# 18_HD4_PUMP.net
KiCad netlist of a schematic drawn in Altium Designer
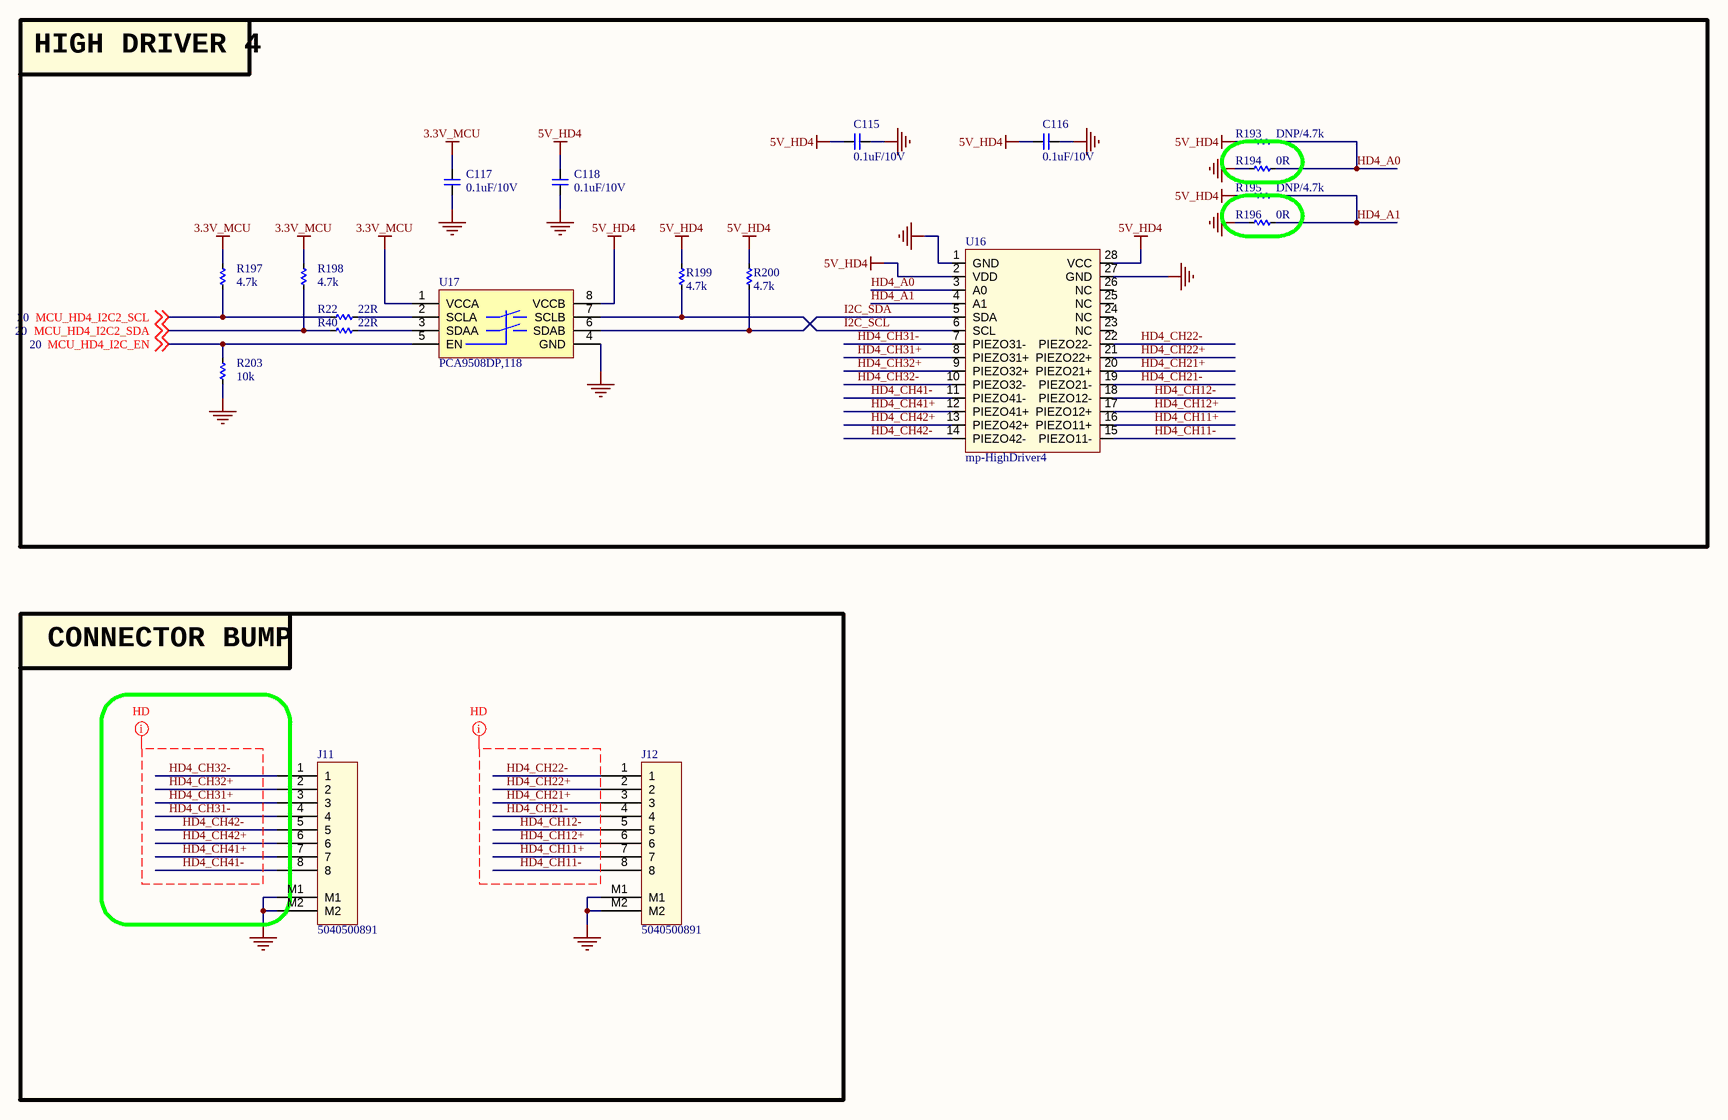
[diagram p0: 18_HD4_PUMP.SchDoc]

(export (version "E")
  (design (tool "Eeschema 10.0.6"))
  (components
    (comp (ref "C115")
      (value "0.1uF/10V")
      (footprint "CAP_C_1005X60")
      (description "CAP")
      (libsource (lib "LABLIB") (part "_CAP_C_2"))
    )
    (comp (ref "C116")
      (value "0.1uF/10V")
      (footprint "CAP_C_1005X60")
      (description "CAP")
      (libsource (lib "LABLIB") (part "_CAP_C_2"))
    )
    (comp (ref "C117")
      (value "0.1uF/10V")
      (footprint "CAP_C_1005X60")
      (description "CAP")
      (libsource (lib "LABLIB") (part "_CAP_C_2"))
    )
    (comp (ref "C118")
      (value "0.1uF/10V")
      (footprint "CAP_C_1005X60")
      (description "CAP")
      (libsource (lib "LABLIB") (part "_CAP_C_2"))
    )
    (comp (ref "J11")
      (value "5040500891")
      (footprint "MOLEX_5040500891")
      (libsource (lib "LABLIB") (part "Header 8x1_2M"))
    )
    (comp (ref "J12")
      (value "5040500891")
      (footprint "MOLEX_5040500891")
      (libsource (lib "LABLIB") (part "Header 8x1_2M"))
    )
    (comp (ref "R22")
      (value "22R")
      (footprint "RES_C_1005X40")
      (description "RES")
      (libsource (lib "LABLIB") (part "_RES_B_2"))
    )
    (comp (ref "R40")
      (value "22R")
      (footprint "RES_C_1005X40")
      (description "RES")
      (libsource (lib "LABLIB") (part "_RES_B_2"))
    )
    (comp (ref "R193")
      (value "DNP/4.7k")
      (footprint "RES_C_1005X40")
      (description "RES")
      (libsource (lib "LABLIB") (part "_RES_B_2"))
    )
    (comp (ref "R194")
      (value "0R")
      (footprint "RES_C_1005X40")
      (description "RES")
      (libsource (lib "LABLIB") (part "_RES_B_2"))
    )
    (comp (ref "R195")
      (value "DNP/4.7k")
      (footprint "RES_C_1005X40")
      (description "RES")
      (libsource (lib "LABLIB") (part "_RES_B_2"))
    )
    (comp (ref "R196")
      (value "0R")
      (footprint "RES_C_1005X40")
      (description "RES")
      (libsource (lib "LABLIB") (part "_RES_B_2"))
    )
    (comp (ref "R197")
      (value "4.7k")
      (footprint "RES_C_1005X40")
      (description "RES")
      (libsource (lib "LABLIB") (part "_RES_B_2"))
    )
    (comp (ref "R198")
      (value "4.7k")
      (footprint "RES_C_1005X40")
      (description "RES")
      (libsource (lib "LABLIB") (part "_RES_B_2"))
    )
    (comp (ref "R199")
      (value "4.7k")
      (footprint "RES_C_1005X40")
      (description "RES")
      (libsource (lib "LABLIB") (part "_RES_B_2"))
    )
    (comp (ref "R200")
      (value "4.7k")
      (footprint "RES_C_1005X40")
      (description "RES")
      (libsource (lib "LABLIB") (part "_RES_B_2"))
    )
    (comp (ref "R203")
      (value "10k")
      (footprint "RES_C_1005X40")
      (description "RES")
      (libsource (lib "LABLIB") (part "_RES_B_2"))
    )
    (comp (ref "U16")
      (value "mp-HighDriver4")
      (footprint "MP_HIGHDRIVER4")
      (libsource (lib "new_component") (part "mp_HighDriver4"))
    )
    (comp (ref "U17")
      (value "PCA9508DP,118")
      (footprint "TSOP8")
      (libsource (lib "EXP_HW_V3") (part "PCA9508DP,118"))
    )
  )
  (nets
    (net (code "1") (name "/HD4_A0") (class "Default")
      (node (ref "R193") (pin "2") (pinfunction "2_2") (pintype "passive"))
      (node (ref "R194") (pin "2") (pinfunction "2_2") (pintype "passive"))
      (node (ref "U16") (pin "3") (pinfunction "A0_3") (pintype "passive"))
    )
    (net (code "2") (name "/HD4_A1") (class "Default")
      (node (ref "R195") (pin "2") (pinfunction "2_2") (pintype "passive"))
      (node (ref "R196") (pin "2") (pinfunction "2_2") (pintype "passive"))
      (node (ref "U16") (pin "4") (pinfunction "A1_4") (pintype "passive"))
    )
    (net (code "3") (name "/HD4_CH11+") (class "Default")
      (node (ref "J12") (pin "7") (pinfunction "7_7") (pintype "passive"))
      (node (ref "U16") (pin "16") (pinfunction "PIEZO11+_16") (pintype "passive"))
    )
    (net (code "4") (name "/HD4_CH11-") (class "Default")
      (node (ref "J12") (pin "8") (pinfunction "8_8") (pintype "passive"))
      (node (ref "U16") (pin "15") (pinfunction "PIEZO11-_15") (pintype "passive"))
    )
    (net (code "5") (name "/HD4_CH12+") (class "Default")
      (node (ref "J12") (pin "6") (pinfunction "6_6") (pintype "passive"))
      (node (ref "U16") (pin "17") (pinfunction "PIEZO12+_17") (pintype "passive"))
    )
    (net (code "6") (name "/HD4_CH12-") (class "Default")
      (node (ref "J12") (pin "5") (pinfunction "5_5") (pintype "passive"))
      (node (ref "U16") (pin "18") (pinfunction "PIEZO12-_18") (pintype "passive"))
    )
    (net (code "7") (name "/HD4_CH21+") (class "Default")
      (node (ref "J12") (pin "3") (pinfunction "3_3") (pintype "passive"))
      (node (ref "U16") (pin "20") (pinfunction "PIEZO21+_20") (pintype "passive"))
    )
    (net (code "8") (name "/HD4_CH21-") (class "Default")
      (node (ref "J12") (pin "4") (pinfunction "4_4") (pintype "passive"))
      (node (ref "U16") (pin "19") (pinfunction "PIEZO21-_19") (pintype "passive"))
    )
    (net (code "9") (name "/HD4_CH22+") (class "Default")
      (node (ref "J12") (pin "2") (pinfunction "2_2") (pintype "passive"))
      (node (ref "U16") (pin "21") (pinfunction "PIEZO22+_21") (pintype "passive"))
    )
    (net (code "10") (name "/HD4_CH22-") (class "Default")
      (node (ref "J12") (pin "1") (pinfunction "1_1") (pintype "passive"))
      (node (ref "U16") (pin "22") (pinfunction "PIEZO22-_22") (pintype "passive"))
    )
    (net (code "11") (name "/HD4_CH31+") (class "Default")
      (node (ref "J11") (pin "3") (pinfunction "3_3") (pintype "passive"))
      (node (ref "U16") (pin "8") (pinfunction "PIEZO31+_8") (pintype "passive"))
    )
    (net (code "12") (name "/HD4_CH31-") (class "Default")
      (node (ref "J11") (pin "4") (pinfunction "4_4") (pintype "passive"))
      (node (ref "U16") (pin "7") (pinfunction "PIEZO31-_7") (pintype "passive"))
    )
    (net (code "13") (name "/HD4_CH32+") (class "Default")
      (node (ref "J11") (pin "2") (pinfunction "2_2") (pintype "passive"))
      (node (ref "U16") (pin "9") (pinfunction "PIEZO32+_9") (pintype "passive"))
    )
    (net (code "14") (name "/HD4_CH32-") (class "Default")
      (node (ref "J11") (pin "1") (pinfunction "1_1") (pintype "passive"))
      (node (ref "U16") (pin "10") (pinfunction "PIEZO32-_10") (pintype "passive"))
    )
    (net (code "15") (name "/HD4_CH41+") (class "Default")
      (node (ref "J11") (pin "7") (pinfunction "7_7") (pintype "passive"))
      (node (ref "U16") (pin "12") (pinfunction "PIEZO41+_12") (pintype "passive"))
    )
    (net (code "16") (name "/HD4_CH41-") (class "Default")
      (node (ref "J11") (pin "8") (pinfunction "8_8") (pintype "passive"))
      (node (ref "U16") (pin "11") (pinfunction "PIEZO41-_11") (pintype "passive"))
    )
    (net (code "17") (name "/HD4_CH42+") (class "Default")
      (node (ref "J11") (pin "6") (pinfunction "6_6") (pintype "passive"))
      (node (ref "U16") (pin "13") (pinfunction "PIEZO42+_13") (pintype "passive"))
    )
    (net (code "18") (name "/HD4_CH42-") (class "Default")
      (node (ref "J11") (pin "5") (pinfunction "5_5") (pintype "passive"))
      (node (ref "U16") (pin "14") (pinfunction "PIEZO42-_14") (pintype "passive"))
    )
    (net (code "19") (name "/I2C_SCL") (class "Default")
      (node (ref "R199") (pin "2") (pinfunction "2_2") (pintype "passive"))
      (node (ref "U16") (pin "6") (pinfunction "SCL_6") (pintype "passive"))
      (node (ref "U17") (pin "7") (pinfunction "SCLB_7") (pintype "passive"))
    )
    (net (code "20") (name "/I2C_SDA") (class "Default")
      (node (ref "R200") (pin "2") (pinfunction "2_2") (pintype "passive"))
      (node (ref "U16") (pin "5") (pinfunction "SDA_5") (pintype "passive"))
      (node (ref "U17") (pin "6") (pinfunction "SDAB_6") (pintype "passive"))
    )
    (net (code "21") (name "3.3V_MCU") (class "Default")
      (node (ref "C117") (pin "2") (pinfunction "2_2") (pintype "passive"))
      (node (ref "R197") (pin "1") (pinfunction "1_1") (pintype "passive"))
      (node (ref "R198") (pin "1") (pinfunction "1_1") (pintype "passive"))
      (node (ref "U17") (pin "1") (pinfunction "VCCA_1") (pintype "passive"))
    )
    (net (code "22") (name "5V_HD4") (class "Default")
      (node (ref "C115") (pin "2") (pinfunction "2_2") (pintype "passive"))
      (node (ref "C116") (pin "2") (pinfunction "2_2") (pintype "passive"))
      (node (ref "C118") (pin "2") (pinfunction "2_2") (pintype "passive"))
      (node (ref "R193") (pin "1") (pinfunction "1_1") (pintype "passive"))
      (node (ref "R195") (pin "1") (pinfunction "1_1") (pintype "passive"))
      (node (ref "R199") (pin "1") (pinfunction "1_1") (pintype "passive"))
      (node (ref "R200") (pin "1") (pinfunction "1_1") (pintype "passive"))
      (node (ref "U16") (pin "2") (pinfunction "VDD_2") (pintype "power_in"))
      (node (ref "U16") (pin "28") (pinfunction "VCC_28") (pintype "power_in"))
      (node (ref "U17") (pin "8") (pinfunction "VCCB_8") (pintype "passive"))
    )
    (net (code "23") (name "GND") (class "Default")
      (node (ref "C115") (pin "1") (pinfunction "1_1") (pintype "passive"))
      (node (ref "C116") (pin "1") (pinfunction "1_1") (pintype "passive"))
      (node (ref "C117") (pin "1") (pinfunction "1_1") (pintype "passive"))
      (node (ref "C118") (pin "1") (pinfunction "1_1") (pintype "passive"))
      (node (ref "J11") (pin "M1") (pinfunction "M1_M1") (pintype "passive"))
      (node (ref "J11") (pin "M2") (pinfunction "M2_M2") (pintype "passive"))
      (node (ref "J12") (pin "M1") (pinfunction "M1_M1") (pintype "passive"))
      (node (ref "J12") (pin "M2") (pinfunction "M2_M2") (pintype "passive"))
      (node (ref "R194") (pin "1") (pinfunction "1_1") (pintype "passive"))
      (node (ref "R196") (pin "1") (pinfunction "1_1") (pintype "passive"))
      (node (ref "R203") (pin "2") (pinfunction "2_2") (pintype "passive"))
      (node (ref "U16") (pin "1") (pinfunction "GND_1") (pintype "power_in"))
      (node (ref "U16") (pin "27") (pinfunction "GND_27") (pintype "power_in"))
      (node (ref "U17") (pin "4") (pinfunction "GND_4") (pintype "passive"))
    )
    (net (code "24") (name "MCU_HD4_I2C2_SCL") (class "Default")
      (node (ref "R197") (pin "2") (pinfunction "2_2") (pintype "passive"))
      (node (ref "R22") (pin "1") (pinfunction "1_1") (pintype "passive"))
    )
    (net (code "25") (name "MCU_HD4_I2C2_SDA") (class "Default")
      (node (ref "R198") (pin "2") (pinfunction "2_2") (pintype "passive"))
      (node (ref "R40") (pin "1") (pinfunction "1_1") (pintype "passive"))
    )
    (net (code "26") (name "MCU_HD4_I2C_EN") (class "Default")
      (node (ref "R203") (pin "1") (pinfunction "1_1") (pintype "passive"))
      (node (ref "U17") (pin "5") (pinfunction "EN_5") (pintype "passive"))
    )
    (net (code "27") (name "Net-(U17-SCLA)") (class "Default")
      (node (ref "R22") (pin "2") (pinfunction "2_2") (pintype "passive"))
      (node (ref "U17") (pin "2") (pinfunction "SCLA_2") (pintype "passive"))
    )
    (net (code "28") (name "Net-(U17-SDAA)") (class "Default")
      (node (ref "R40") (pin "2") (pinfunction "2_2") (pintype "passive"))
      (node (ref "U17") (pin "3") (pinfunction "SDAA_3") (pintype "passive"))
    )
    (net (code "29") (name "unconnected-(U16-NC-Pad23)") (class "Default")
      (node (ref "U16") (pin "23") (pinfunction "NC_23") (pintype "passive"))
    )
    (net (code "30") (name "unconnected-(U16-NC-Pad24)") (class "Default")
      (node (ref "U16") (pin "24") (pinfunction "NC_24") (pintype "passive"))
    )
    (net (code "31") (name "unconnected-(U16-NC-Pad25)") (class "Default")
      (node (ref "U16") (pin "25") (pinfunction "NC_25") (pintype "passive"))
    )
    (net (code "32") (name "unconnected-(U16-NC-Pad26)") (class "Default")
      (node (ref "U16") (pin "26") (pinfunction "NC_26") (pintype "passive"))
    )
  )
)
